# micro.net
KiCad netlist of a schematic drawn in Altium Designer
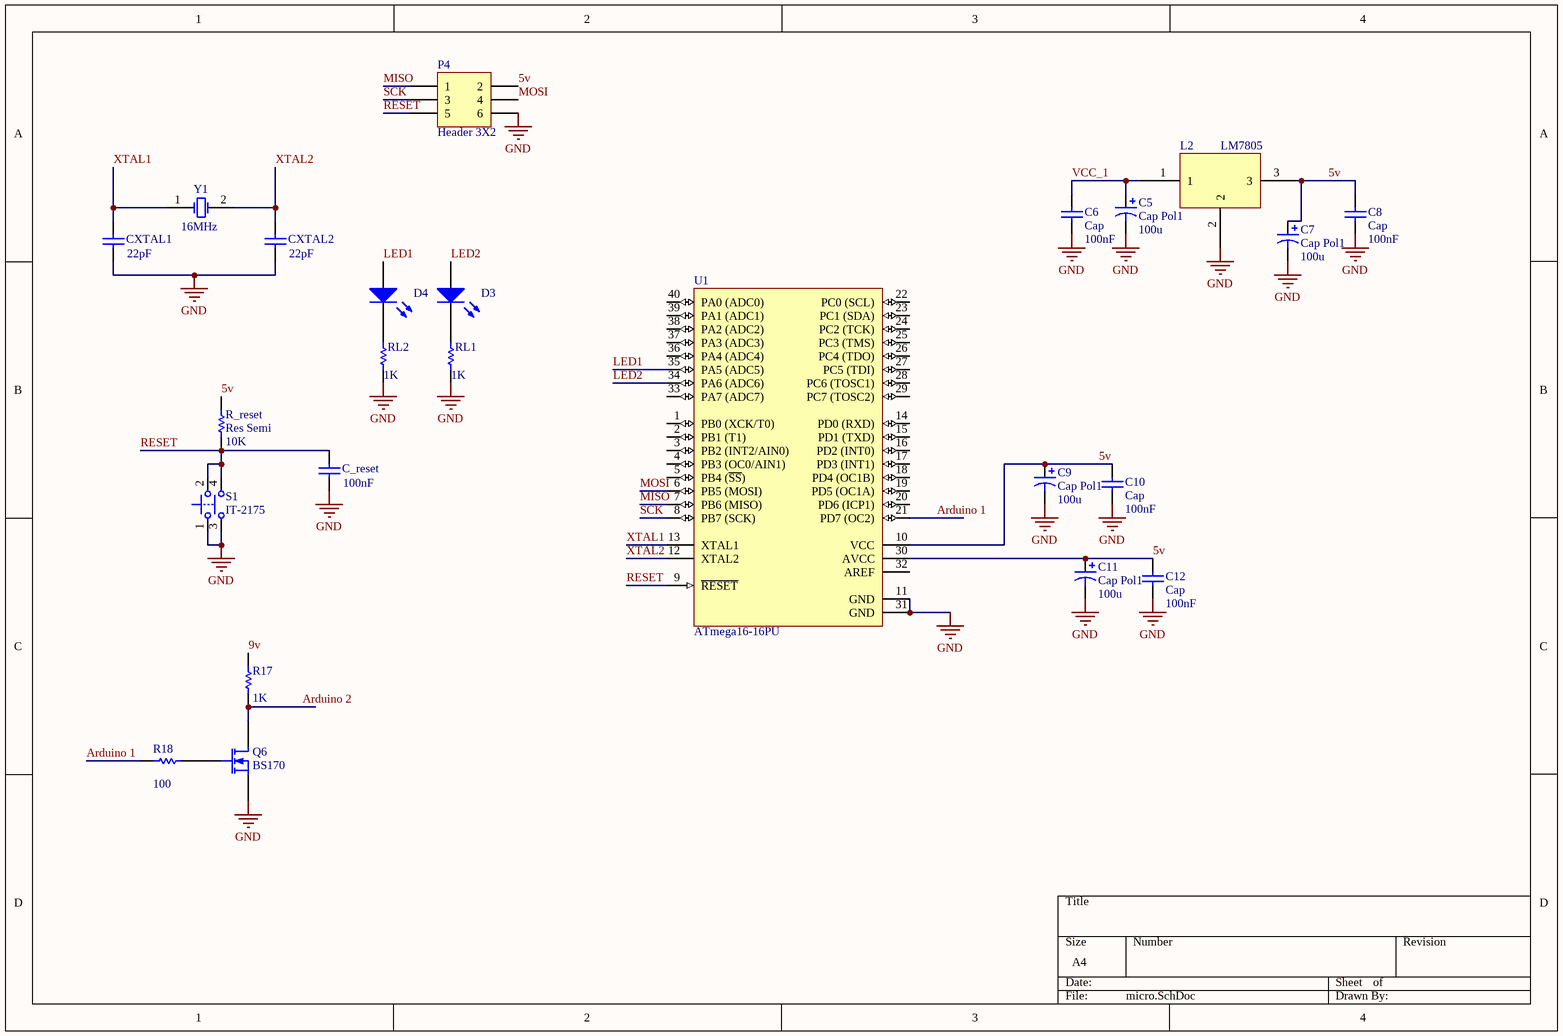
[diagram p0: micro.SchDoc]

(export (version "E")
  (design (tool "Eeschema 10.0.6"))
  (components
    (comp (ref "C5")
      (value "Cap Pol1")
      (footprint "A")
      (description "Polarized Capacitor (Radial)")
      (fields (field (name "ALTIUM_VALUE") "100u") (field (name "PUBLISHER") "Altium Limited"))
      (libsource (lib "Miscellaneous Devices") (part "Cap Pol1"))
    )
    (comp (ref "C6")
      (value "Cap")
      (footprint "C1206")
      (description "Capacitor")
      (fields (field (name "ALTIUM_VALUE") "100nF") (field (name "PUBLISHER") "Altium Limited"))
      (libsource (lib "Miscellaneous Devices") (part "Cap"))
    )
    (comp (ref "C7")
      (value "Cap Pol1")
      (footprint "A")
      (description "Polarized Capacitor (Radial)")
      (fields (field (name "ALTIUM_VALUE") "100u") (field (name "PUBLISHER") "Altium Limited"))
      (libsource (lib "Miscellaneous Devices") (part "Cap Pol1"))
    )
    (comp (ref "C8")
      (value "Cap")
      (footprint "C1206")
      (description "Capacitor")
      (fields (field (name "ALTIUM_VALUE") "100nF") (field (name "PUBLISHER") "Altium Limited"))
      (libsource (lib "Miscellaneous Devices") (part "Cap"))
    )
    (comp (ref "C9")
      (value "Cap Pol1")
      (footprint "A")
      (description "Polarized Capacitor (Radial)")
      (fields (field (name "ALTIUM_VALUE") "100u") (field (name "PUBLISHER") "Altium Limited"))
      (libsource (lib "Miscellaneous Devices") (part "Cap Pol1"))
    )
    (comp (ref "C10")
      (value "Cap")
      (footprint "C1206")
      (description "Capacitor")
      (fields (field (name "ALTIUM_VALUE") "100nF") (field (name "PUBLISHER") "Altium Limited"))
      (libsource (lib "Miscellaneous Devices") (part "Cap"))
    )
    (comp (ref "C11")
      (value "Cap Pol1")
      (footprint "A")
      (description "Polarized Capacitor (Radial)")
      (fields (field (name "ALTIUM_VALUE") "100u") (field (name "PUBLISHER") "Altium Limited"))
      (libsource (lib "Miscellaneous Devices") (part "Cap Pol1"))
    )
    (comp (ref "C12")
      (value "Cap")
      (footprint "C1206")
      (description "Capacitor")
      (fields (field (name "ALTIUM_VALUE") "100nF") (field (name "PUBLISHER") "Altium Limited"))
      (libsource (lib "Miscellaneous Devices") (part "Cap"))
    )
    (comp (ref "CXTAL1")
      (value "22pF")
      (footprint "C1206")
      (description "Capacitor (Semiconductor SIM Model)")
      (fields (field (name "Comment") "Ci") (field (name "PUBLISHER") "Altium Limited"))
      (libsource (lib "Miscellaneous Devices") (part "Cap Semi"))
    )
    (comp (ref "CXTAL2")
      (value "22pF")
      (footprint "C1206")
      (description "Capacitor (Semiconductor SIM Model)")
      (fields (field (name "Comment") "Ci") (field (name "PUBLISHER") "Altium Limited"))
      (libsource (lib "Miscellaneous Devices") (part "Cap Semi"))
    )
    (comp (ref "C_reset")
      (value "100nF")
      (footprint "C1206")
      (description "Capacitor (Semiconductor SIM Model)")
      (fields (field (name "Comment") "Ci") (field (name "PUBLISHER") "Altium Limited"))
      (libsource (lib "Miscellaneous Devices") (part "Cap Semi"))
    )
    (comp (ref "D3")
      (value "LED3")
      (footprint "LED Blue 3mm TH V")
      (description "Typical BLUE SiC LED")
      (fields (field (name "PUBLISHER") "Altium Limited"))
      (libsource (lib "Miscellaneous Devices") (part "LED3"))
    )
    (comp (ref "D4")
      (value "LED3")
      (footprint "LED Blue 3mm TH V")
      (description "Typical BLUE SiC LED")
      (fields (field (name "PUBLISHER") "Altium Limited"))
      (libsource (lib "Miscellaneous Devices") (part "LED3"))
    )
    (comp (ref "L2") (value "LM7805") (footprint "TO-220AB") (libsource (lib "LM7809") (part "LM7809")))
    (comp (ref "P4")
      (value "Header 3X2")
      (footprint "HDR2X3")
      (description "Header, 3-Pin, Dual row")
      (fields (field (name "PUBLISHER") "Altium Limited"))
      (libsource (lib "Miscellaneous Connectors") (part "Header 3X2"))
    )
    (comp (ref "Q6")
      (value "BS170")
      (footprint "E3")
      (description "N-Channel MOSFET")
      (fields (field (name "PUBLISHER") "Altium Limited"))
      (libsource (lib "Miscellaneous Devices") (part "MOSFET-N"))
    )
    (comp (ref "R17")
      (value "1K")
      (footprint "3216[1206]")
      (description "Semiconductor Resistor")
      (fields (field (name "Comment") "Res Semi") (field (name "PUBLISHER") "Altium Limited"))
      (libsource (lib "Miscellaneous Devices") (part "Res Semi"))
    )
    (comp (ref "R18")
      (value "100")
      (footprint "3216[1206]")
      (description "Semiconductor Resistor")
      (fields (field (name "Comment") "Res Semi") (field (name "PUBLISHER") "Altium Limited"))
      (libsource (lib "Miscellaneous Devices") (part "Res Semi"))
    )
    (comp (ref "RL1")
      (value "1K")
      (footprint "3216[1206]")
      (description "Semiconductor Resistor")
      (fields (field (name "Comment") "Res Semi") (field (name "PUBLISHER") "Altium Limited"))
      (libsource (lib "Miscellaneous Devices") (part "Res Semi"))
    )
    (comp (ref "RL2")
      (value "1K")
      (footprint "3216[1206]")
      (description "Semiconductor Resistor")
      (fields (field (name "Comment") "Res Semi") (field (name "PUBLISHER") "Altium Limited"))
      (libsource (lib "Miscellaneous Devices") (part "Res Semi"))
    )
    (comp (ref "R_reset")
      (value "Res Semi")
      (footprint "3216[1206]")
      (description "Semiconductor Resistor")
      (fields (field (name "ALTIUM_VALUE") "10K") (field (name "PUBLISHER") "Altium Limited"))
      (libsource (lib "Miscellaneous Devices") (part "Res Semi"))
    )
    (comp (ref "S1")
      (value "IT-2175")
      (footprint "IT-2175")
      (description "Tactile Switch, DPST; Thru-Hole; Vertical; Rating DC 12V, 50mA (max)")
      (fields (field (name "PUBLISHER") "Altium Limited"))
      (libsource (lib "IL Switch Push Button") (part "IT-2175"))
    )
    (comp (ref "U1")
      (value "ATmega16-16PU")
      (footprint "40P6")
      (libsource (lib "Atmel Microcontroller megaAVR") (part "ATmega16-16PU"))
    )
    (comp (ref "Y1")
      (value "16MHz")
      (footprint "R38")
      (description "Crystal Oscillator")
      (fields (field (name "PUBLISHER") "Altium Limited"))
      (libsource (lib "Miscellaneous Devices") (part "XTAL"))
    )
  )
  (nets
    (net (code "1") (name "/5v") (class "Default")
      (node (ref "C10") (pin "2") (pinfunction "2_2") (pintype "passive"))
      (node (ref "C11") (pin "1") (pinfunction "1_1") (pintype "passive"))
      (node (ref "C12") (pin "2") (pinfunction "2_2") (pintype "passive"))
      (node (ref "C7") (pin "1") (pinfunction "1_1") (pintype "passive"))
      (node (ref "C8") (pin "2") (pinfunction "2_2") (pintype "passive"))
      (node (ref "C9") (pin "1") (pinfunction "1_1") (pintype "passive"))
      (node (ref "L2") (pin "3") (pinfunction "3_3") (pintype "passive"))
      (node (ref "P4") (pin "2") (pinfunction "2_2") (pintype "passive"))
      (node (ref "R_reset") (pin "2") (pinfunction "2_2") (pintype "passive"))
      (node (ref "U1") (pin "10") (pinfunction "VCC_10") (pintype "power_in"))
      (node (ref "U1") (pin "30") (pinfunction "AVCC_30") (pintype "power_in"))
    )
    (net (code "2") (name "/9v") (class "Default")
      (node (ref "R17") (pin "2") (pinfunction "2_2") (pintype "passive"))
    )
    (net (code "3") (name "/Arduino 1") (class "Default")
      (node (ref "R18") (pin "2") (pinfunction "2_2") (pintype "passive"))
      (node (ref "U1") (pin "21") (pinfunction "PD7_(OC2)_21") (pintype "bidirectional"))
    )
    (net (code "4") (name "/Arduino 2") (class "Default")
      (node (ref "Q6") (pin "1") (pinfunction "D_1") (pintype "passive"))
      (node (ref "R17") (pin "1") (pinfunction "1_1") (pintype "passive"))
    )
    (net (code "5") (name "/LED1") (class "Default")
      (node (ref "D4") (pin "1") (pinfunction "A_1") (pintype "passive"))
      (node (ref "U1") (pin "35") (pinfunction "PA5_(ADC5)_35") (pintype "bidirectional"))
    )
    (net (code "6") (name "/LED2") (class "Default")
      (node (ref "D3") (pin "1") (pinfunction "A_1") (pintype "passive"))
      (node (ref "U1") (pin "34") (pinfunction "PA6_(ADC6)_34") (pintype "bidirectional"))
    )
    (net (code "7") (name "/MISO") (class "Default")
      (node (ref "P4") (pin "1") (pinfunction "1_1") (pintype "passive"))
      (node (ref "U1") (pin "7") (pinfunction "PB6_(MISO)_7") (pintype "bidirectional"))
    )
    (net (code "8") (name "/MOSI") (class "Default")
      (node (ref "P4") (pin "4") (pinfunction "4_4") (pintype "passive"))
      (node (ref "U1") (pin "6") (pinfunction "PB5_(MOSI)_6") (pintype "bidirectional"))
    )
    (net (code "9") (name "/RESET") (class "Default")
      (node (ref "C_reset") (pin "2") (pinfunction "2_2") (pintype "passive"))
      (node (ref "P4") (pin "5") (pinfunction "5_5") (pintype "passive"))
      (node (ref "R_reset") (pin "1") (pinfunction "1_1") (pintype "passive"))
      (node (ref "S1") (pin "2") (pinfunction "2_2") (pintype "passive"))
      (node (ref "S1") (pin "4") (pinfunction "4_4") (pintype "passive"))
      (node (ref "U1") (pin "9") (pinfunction "~{RESET}_9") (pintype "input"))
    )
    (net (code "10") (name "/SCK") (class "Default")
      (node (ref "P4") (pin "3") (pinfunction "3_3") (pintype "passive"))
      (node (ref "U1") (pin "8") (pinfunction "PB7_(SCK)_8") (pintype "bidirectional"))
    )
    (net (code "11") (name "/VCC_1") (class "Default")
      (node (ref "C5") (pin "1") (pinfunction "1_1") (pintype "passive"))
      (node (ref "C6") (pin "2") (pinfunction "2_2") (pintype "passive"))
      (node (ref "L2") (pin "1") (pinfunction "1_1") (pintype "passive"))
    )
    (net (code "12") (name "/XTAL1") (class "Default")
      (node (ref "CXTAL1") (pin "2") (pinfunction "2_2") (pintype "passive"))
      (node (ref "U1") (pin "13") (pinfunction "XTAL1_13") (pintype "passive"))
      (node (ref "Y1") (pin "1") (pinfunction "OSC1_1") (pintype "passive"))
    )
    (net (code "13") (name "/XTAL2") (class "Default")
      (node (ref "CXTAL2") (pin "2") (pinfunction "2_2") (pintype "passive"))
      (node (ref "U1") (pin "12") (pinfunction "XTAL2_12") (pintype "passive"))
      (node (ref "Y1") (pin "2") (pinfunction "OSC2_2") (pintype "passive"))
    )
    (net (code "14") (name "GND") (class "Default")
      (node (ref "C10") (pin "1") (pinfunction "1_1") (pintype "passive"))
      (node (ref "C11") (pin "2") (pinfunction "2_2") (pintype "passive"))
      (node (ref "C12") (pin "1") (pinfunction "1_1") (pintype "passive"))
      (node (ref "C5") (pin "2") (pinfunction "2_2") (pintype "passive"))
      (node (ref "C6") (pin "1") (pinfunction "1_1") (pintype "passive"))
      (node (ref "C7") (pin "2") (pinfunction "2_2") (pintype "passive"))
      (node (ref "C8") (pin "1") (pinfunction "1_1") (pintype "passive"))
      (node (ref "C9") (pin "2") (pinfunction "2_2") (pintype "passive"))
      (node (ref "CXTAL1") (pin "1") (pinfunction "1_1") (pintype "passive"))
      (node (ref "CXTAL2") (pin "1") (pinfunction "1_1") (pintype "passive"))
      (node (ref "C_reset") (pin "1") (pinfunction "1_1") (pintype "passive"))
      (node (ref "L2") (pin "2") (pinfunction "2_2") (pintype "passive"))
      (node (ref "P4") (pin "6") (pinfunction "6_6") (pintype "passive"))
      (node (ref "Q6") (pin "3") (pinfunction "S_3") (pintype "passive"))
      (node (ref "RL1") (pin "1") (pinfunction "1_1") (pintype "passive"))
      (node (ref "RL2") (pin "1") (pinfunction "1_1") (pintype "passive"))
      (node (ref "S1") (pin "1") (pinfunction "1_1") (pintype "passive"))
      (node (ref "S1") (pin "3") (pinfunction "3_3") (pintype "passive"))
      (node (ref "U1") (pin "11") (pinfunction "GND_11") (pintype "power_in"))
      (node (ref "U1") (pin "31") (pinfunction "GND_31") (pintype "power_in"))
    )
    (net (code "15") (name "Net-(D3-K)") (class "Default")
      (node (ref "D3") (pin "2") (pinfunction "K_2") (pintype "passive"))
      (node (ref "RL1") (pin "2") (pinfunction "2_2") (pintype "passive"))
    )
    (net (code "16") (name "Net-(D4-K)") (class "Default")
      (node (ref "D4") (pin "2") (pinfunction "K_2") (pintype "passive"))
      (node (ref "RL2") (pin "2") (pinfunction "2_2") (pintype "passive"))
    )
    (net (code "17") (name "Net-(Q6-G)") (class "Default")
      (node (ref "Q6") (pin "2") (pinfunction "G_2") (pintype "passive"))
      (node (ref "R18") (pin "1") (pinfunction "1_1") (pintype "passive"))
    )
    (net (code "18") (name "unconnected-(U1-AREF-Pad32)") (class "Default")
      (node (ref "U1") (pin "32") (pinfunction "AREF_32") (pintype "power_in"))
    )
    (net (code "19") (name "unconnected-(U1-PA0_(ADC0)-Pad40)") (class "Default")
      (node (ref "U1") (pin "40") (pinfunction "PA0_(ADC0)_40") (pintype "bidirectional"))
    )
    (net (code "20") (name "unconnected-(U1-PA1_(ADC1)-Pad39)") (class "Default")
      (node (ref "U1") (pin "39") (pinfunction "PA1_(ADC1)_39") (pintype "bidirectional"))
    )
    (net (code "21") (name "unconnected-(U1-PA2_(ADC2)-Pad38)") (class "Default")
      (node (ref "U1") (pin "38") (pinfunction "PA2_(ADC2)_38") (pintype "bidirectional"))
    )
    (net (code "22") (name "unconnected-(U1-PA3_(ADC3)-Pad37)") (class "Default")
      (node (ref "U1") (pin "37") (pinfunction "PA3_(ADC3)_37") (pintype "bidirectional"))
    )
    (net (code "23") (name "unconnected-(U1-PA4_(ADC4)-Pad36)") (class "Default")
      (node (ref "U1") (pin "36") (pinfunction "PA4_(ADC4)_36") (pintype "bidirectional"))
    )
    (net (code "24") (name "unconnected-(U1-PA7_(ADC7)-Pad33)") (class "Default")
      (node (ref "U1") (pin "33") (pinfunction "PA7_(ADC7)_33") (pintype "bidirectional"))
    )
    (net (code "25") (name "unconnected-(U1-PB0_(XCK{slash}T0)-Pad1)") (class "Default")
      (node (ref "U1") (pin "1") (pinfunction "PB0_(XCK/T0)_1") (pintype "bidirectional"))
    )
    (net (code "26") (name "unconnected-(U1-PB1_(T1)-Pad2)") (class "Default")
      (node (ref "U1") (pin "2") (pinfunction "PB1_(T1)_2") (pintype "bidirectional"))
    )
    (net (code "27") (name "unconnected-(U1-PB2_(INT2{slash}AIN0)-Pad3)") (class "Default")
      (node (ref "U1") (pin "3") (pinfunction "PB2_(INT2/AIN0)_3") (pintype "bidirectional"))
    )
    (net (code "28") (name "unconnected-(U1-PB3_(OC0{slash}AIN1)-Pad4)") (class "Default")
      (node (ref "U1") (pin "4") (pinfunction "PB3_(OC0/AIN1)_4") (pintype "bidirectional"))
    )
    (net (code "29") (name "unconnected-(U1-PB4_(~{SS})-Pad5)") (class "Default")
      (node (ref "U1") (pin "5") (pinfunction "PB4_(~{SS})_5") (pintype "bidirectional"))
    )
    (net (code "30") (name "unconnected-(U1-PC0_(SCL)-Pad22)") (class "Default")
      (node (ref "U1") (pin "22") (pinfunction "PC0_(SCL)_22") (pintype "bidirectional"))
    )
    (net (code "31") (name "unconnected-(U1-PC1_(SDA)-Pad23)") (class "Default")
      (node (ref "U1") (pin "23") (pinfunction "PC1_(SDA)_23") (pintype "bidirectional"))
    )
    (net (code "32") (name "unconnected-(U1-PC2_(TCK)-Pad24)") (class "Default")
      (node (ref "U1") (pin "24") (pinfunction "PC2_(TCK)_24") (pintype "bidirectional"))
    )
    (net (code "33") (name "unconnected-(U1-PC3_(TMS)-Pad25)") (class "Default")
      (node (ref "U1") (pin "25") (pinfunction "PC3_(TMS)_25") (pintype "bidirectional"))
    )
    (net (code "34") (name "unconnected-(U1-PC4_(TDO)-Pad26)") (class "Default")
      (node (ref "U1") (pin "26") (pinfunction "PC4_(TDO)_26") (pintype "bidirectional"))
    )
    (net (code "35") (name "unconnected-(U1-PC5_(TDI)-Pad27)") (class "Default")
      (node (ref "U1") (pin "27") (pinfunction "PC5_(TDI)_27") (pintype "bidirectional"))
    )
    (net (code "36") (name "unconnected-(U1-PC6_(TOSC1)-Pad28)") (class "Default")
      (node (ref "U1") (pin "28") (pinfunction "PC6_(TOSC1)_28") (pintype "bidirectional"))
    )
    (net (code "37") (name "unconnected-(U1-PC7_(TOSC2)-Pad29)") (class "Default")
      (node (ref "U1") (pin "29") (pinfunction "PC7_(TOSC2)_29") (pintype "bidirectional"))
    )
    (net (code "38") (name "unconnected-(U1-PD0_(RXD)-Pad14)") (class "Default")
      (node (ref "U1") (pin "14") (pinfunction "PD0_(RXD)_14") (pintype "bidirectional"))
    )
    (net (code "39") (name "unconnected-(U1-PD1_(TXD)-Pad15)") (class "Default")
      (node (ref "U1") (pin "15") (pinfunction "PD1_(TXD)_15") (pintype "bidirectional"))
    )
    (net (code "40") (name "unconnected-(U1-PD2_(INT0)-Pad16)") (class "Default")
      (node (ref "U1") (pin "16") (pinfunction "PD2_(INT0)_16") (pintype "bidirectional"))
    )
    (net (code "41") (name "unconnected-(U1-PD3_(INT1)-Pad17)") (class "Default")
      (node (ref "U1") (pin "17") (pinfunction "PD3_(INT1)_17") (pintype "bidirectional"))
    )
    (net (code "42") (name "unconnected-(U1-PD4_(OC1B)-Pad18)") (class "Default")
      (node (ref "U1") (pin "18") (pinfunction "PD4_(OC1B)_18") (pintype "bidirectional"))
    )
    (net (code "43") (name "unconnected-(U1-PD5_(OC1A)-Pad19)") (class "Default")
      (node (ref "U1") (pin "19") (pinfunction "PD5_(OC1A)_19") (pintype "bidirectional"))
    )
    (net (code "44") (name "unconnected-(U1-PD6_(ICP1)-Pad20)") (class "Default")
      (node (ref "U1") (pin "20") (pinfunction "PD6_(ICP1)_20") (pintype "bidirectional"))
    )
  )
)
